# lc_filter_final.net
KiCad netlist of a schematic drawn in EAGLE
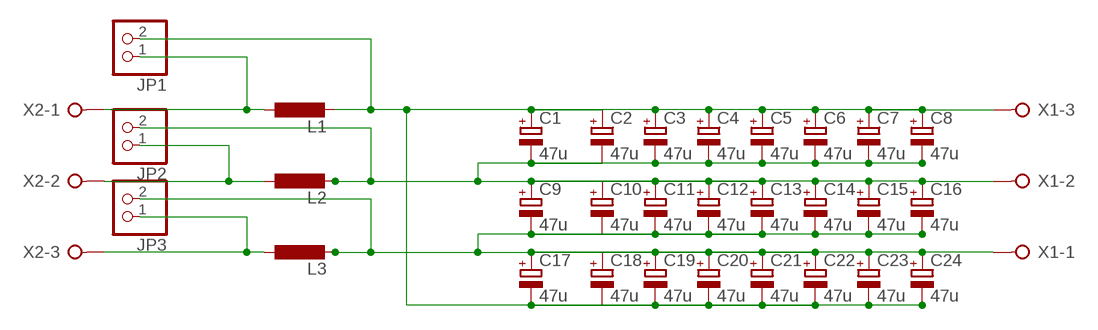
[diagram p0: schematic, sheet 1]

(export (version "E")
  (design (tool "Eeschema 10.0.6"))
  (components
    (comp (ref "C1")
      (value "47u")
      (footprint "eagle-import:E5-10,5")
      (libsource (lib "eagle-import") (part "CPOL-EUE5-10.5"))
    )
    (comp (ref "C2")
      (value "47u")
      (footprint "eagle-import:E5-10,5")
      (libsource (lib "eagle-import") (part "CPOL-EUE5-10.5"))
    )
    (comp (ref "C3")
      (value "47u")
      (footprint "eagle-import:E5-10,5")
      (libsource (lib "eagle-import") (part "CPOL-EUE5-10.5"))
    )
    (comp (ref "C4")
      (value "47u")
      (footprint "eagle-import:E5-10,5")
      (libsource (lib "eagle-import") (part "CPOL-EUE5-10.5"))
    )
    (comp (ref "C5")
      (value "47u")
      (footprint "eagle-import:E5-10,5")
      (libsource (lib "eagle-import") (part "CPOL-EUE5-10.5"))
    )
    (comp (ref "C6")
      (value "47u")
      (footprint "eagle-import:E5-10,5")
      (libsource (lib "eagle-import") (part "CPOL-EUE5-10.5"))
    )
    (comp (ref "C7")
      (value "47u")
      (footprint "eagle-import:E5-10,5")
      (libsource (lib "eagle-import") (part "CPOL-EUE5-10.5"))
    )
    (comp (ref "C8")
      (value "47u")
      (footprint "eagle-import:E5-10,5")
      (libsource (lib "eagle-import") (part "CPOL-EUE5-10.5"))
    )
    (comp (ref "C9")
      (value "47u")
      (footprint "eagle-import:E5-10,5")
      (libsource (lib "eagle-import") (part "CPOL-EUE5-10.5"))
    )
    (comp (ref "C10")
      (value "47u")
      (footprint "eagle-import:E5-10,5")
      (libsource (lib "eagle-import") (part "CPOL-EUE5-10.5"))
    )
    (comp (ref "C11")
      (value "47u")
      (footprint "eagle-import:E5-10,5")
      (libsource (lib "eagle-import") (part "CPOL-EUE5-10.5"))
    )
    (comp (ref "C12")
      (value "47u")
      (footprint "eagle-import:E5-10,5")
      (libsource (lib "eagle-import") (part "CPOL-EUE5-10.5"))
    )
    (comp (ref "C13")
      (value "47u")
      (footprint "eagle-import:E5-10,5")
      (libsource (lib "eagle-import") (part "CPOL-EUE5-10.5"))
    )
    (comp (ref "C14")
      (value "47u")
      (footprint "eagle-import:E5-10,5")
      (libsource (lib "eagle-import") (part "CPOL-EUE5-10.5"))
    )
    (comp (ref "C15")
      (value "47u")
      (footprint "eagle-import:E5-10,5")
      (libsource (lib "eagle-import") (part "CPOL-EUE5-10.5"))
    )
    (comp (ref "C16")
      (value "47u")
      (footprint "eagle-import:E5-10,5")
      (libsource (lib "eagle-import") (part "CPOL-EUE5-10.5"))
    )
    (comp (ref "C17")
      (value "47u")
      (footprint "eagle-import:E5-10,5")
      (libsource (lib "eagle-import") (part "CPOL-EUE5-10.5"))
    )
    (comp (ref "C18")
      (value "47u")
      (footprint "eagle-import:E5-10,5")
      (libsource (lib "eagle-import") (part "CPOL-EUE5-10.5"))
    )
    (comp (ref "C19")
      (value "47u")
      (footprint "eagle-import:E5-10,5")
      (libsource (lib "eagle-import") (part "CPOL-EUE5-10.5"))
    )
    (comp (ref "C20")
      (value "47u")
      (footprint "eagle-import:E5-10,5")
      (libsource (lib "eagle-import") (part "CPOL-EUE5-10.5"))
    )
    (comp (ref "C21")
      (value "47u")
      (footprint "eagle-import:E5-10,5")
      (libsource (lib "eagle-import") (part "CPOL-EUE5-10.5"))
    )
    (comp (ref "C22")
      (value "47u")
      (footprint "eagle-import:E5-10,5")
      (libsource (lib "eagle-import") (part "CPOL-EUE5-10.5"))
    )
    (comp (ref "C23")
      (value "47u")
      (footprint "eagle-import:E5-10,5")
      (libsource (lib "eagle-import") (part "CPOL-EUE5-10.5"))
    )
    (comp (ref "C24")
      (value "47u")
      (footprint "eagle-import:E5-10,5")
      (libsource (lib "eagle-import") (part "CPOL-EUE5-10.5"))
    )
    (comp (ref "JP1")
      (value "PINHD-1X2")
      (footprint "eagle-import:1X02")
      (libsource (lib "eagle-import") (part "PINHD-1X2"))
    )
    (comp (ref "JP2")
      (value "PINHD-1X2")
      (footprint "eagle-import:1X02")
      (libsource (lib "eagle-import") (part "PINHD-1X2"))
    )
    (comp (ref "JP3")
      (value "PINHD-1X2")
      (footprint "eagle-import:1X02")
      (libsource (lib "eagle-import") (part "PINHD-1X2"))
    )
    (comp (ref "L1")
      (value "L-EU6000-XXX-RC")
      (footprint "eagle-import:6000-XXXX-RC")
      (libsource (lib "eagle-import") (part "L-EU6000-XXX-RC"))
    )
    (comp (ref "L2")
      (value "L-EU6000-XXX-RC")
      (footprint "eagle-import:6000-XXXX-RC")
      (libsource (lib "eagle-import") (part "L-EU6000-XXX-RC"))
    )
    (comp (ref "L3")
      (value "L-EU6000-XXX-RC")
      (footprint "eagle-import:6000-XXXX-RC")
      (libsource (lib "eagle-import") (part "L-EU6000-XXX-RC"))
    )
    (comp (ref "X1")
      (value "W237-03P")
      (footprint "eagle-import:W237-133")
      (libsource (lib "eagle-import") (part "W237-03P"))
    )
    (comp (ref "X2")
      (value "W237-03P")
      (footprint "eagle-import:W237-133")
      (libsource (lib "eagle-import") (part "W237-03P"))
    )
  )
  (nets
    (net (code "1") (name "Net-(X1A-KL)") (class "Default")
      (node (ref "C10") (pin "-") (pinfunction "-_-") (pintype "passive"))
      (node (ref "C11") (pin "-") (pinfunction "-_-") (pintype "passive"))
      (node (ref "C12") (pin "-") (pinfunction "-_-") (pintype "passive"))
      (node (ref "C13") (pin "-") (pinfunction "-_-") (pintype "passive"))
      (node (ref "C14") (pin "-") (pinfunction "-_-") (pintype "passive"))
      (node (ref "C15") (pin "-") (pinfunction "-_-") (pintype "passive"))
      (node (ref "C16") (pin "-") (pinfunction "-_-") (pintype "passive"))
      (node (ref "C17") (pin "+") (pinfunction "+_+") (pintype "passive"))
      (node (ref "C18") (pin "+") (pinfunction "+_+") (pintype "passive"))
      (node (ref "C19") (pin "+") (pinfunction "+_+") (pintype "passive"))
      (node (ref "C20") (pin "+") (pinfunction "+_+") (pintype "passive"))
      (node (ref "C21") (pin "+") (pinfunction "+_+") (pintype "passive"))
      (node (ref "C22") (pin "+") (pinfunction "+_+") (pintype "passive"))
      (node (ref "C23") (pin "+") (pinfunction "+_+") (pintype "passive"))
      (node (ref "C24") (pin "+") (pinfunction "+_+") (pintype "passive"))
      (node (ref "C9") (pin "-") (pinfunction "-_-") (pintype "passive"))
      (node (ref "JP3") (pin "2") (pinfunction "2_2") (pintype "passive"))
      (node (ref "L3") (pin "2") (pinfunction "2_2") (pintype "passive"))
      (node (ref "X1") (pin "1") (pinfunction "KL_1") (pintype "passive"))
    )
    (net (code "2") (name "Net-(X1B-KL)") (class "Default")
      (node (ref "C1") (pin "-") (pinfunction "-_-") (pintype "passive"))
      (node (ref "C10") (pin "+") (pinfunction "+_+") (pintype "passive"))
      (node (ref "C11") (pin "+") (pinfunction "+_+") (pintype "passive"))
      (node (ref "C12") (pin "+") (pinfunction "+_+") (pintype "passive"))
      (node (ref "C13") (pin "+") (pinfunction "+_+") (pintype "passive"))
      (node (ref "C14") (pin "+") (pinfunction "+_+") (pintype "passive"))
      (node (ref "C15") (pin "+") (pinfunction "+_+") (pintype "passive"))
      (node (ref "C16") (pin "+") (pinfunction "+_+") (pintype "passive"))
      (node (ref "C2") (pin "-") (pinfunction "-_-") (pintype "passive"))
      (node (ref "C3") (pin "-") (pinfunction "-_-") (pintype "passive"))
      (node (ref "C4") (pin "-") (pinfunction "-_-") (pintype "passive"))
      (node (ref "C5") (pin "-") (pinfunction "-_-") (pintype "passive"))
      (node (ref "C6") (pin "-") (pinfunction "-_-") (pintype "passive"))
      (node (ref "C7") (pin "-") (pinfunction "-_-") (pintype "passive"))
      (node (ref "C8") (pin "-") (pinfunction "-_-") (pintype "passive"))
      (node (ref "C9") (pin "+") (pinfunction "+_+") (pintype "passive"))
      (node (ref "JP2") (pin "2") (pinfunction "2_2") (pintype "passive"))
      (node (ref "L2") (pin "2") (pinfunction "2_2") (pintype "passive"))
      (node (ref "X1") (pin "2") (pinfunction "KL_2") (pintype "passive"))
    )
    (net (code "3") (name "Net-(X1C-KL)") (class "Default")
      (node (ref "C1") (pin "+") (pinfunction "+_+") (pintype "passive"))
      (node (ref "C17") (pin "-") (pinfunction "-_-") (pintype "passive"))
      (node (ref "C18") (pin "-") (pinfunction "-_-") (pintype "passive"))
      (node (ref "C19") (pin "-") (pinfunction "-_-") (pintype "passive"))
      (node (ref "C2") (pin "+") (pinfunction "+_+") (pintype "passive"))
      (node (ref "C20") (pin "-") (pinfunction "-_-") (pintype "passive"))
      (node (ref "C21") (pin "-") (pinfunction "-_-") (pintype "passive"))
      (node (ref "C22") (pin "-") (pinfunction "-_-") (pintype "passive"))
      (node (ref "C23") (pin "-") (pinfunction "-_-") (pintype "passive"))
      (node (ref "C24") (pin "-") (pinfunction "-_-") (pintype "passive"))
      (node (ref "C3") (pin "+") (pinfunction "+_+") (pintype "passive"))
      (node (ref "C4") (pin "+") (pinfunction "+_+") (pintype "passive"))
      (node (ref "C5") (pin "+") (pinfunction "+_+") (pintype "passive"))
      (node (ref "C6") (pin "+") (pinfunction "+_+") (pintype "passive"))
      (node (ref "C7") (pin "+") (pinfunction "+_+") (pintype "passive"))
      (node (ref "C8") (pin "+") (pinfunction "+_+") (pintype "passive"))
      (node (ref "JP1") (pin "2") (pinfunction "2_2") (pintype "passive"))
      (node (ref "L1") (pin "2") (pinfunction "2_2") (pintype "passive"))
      (node (ref "X1") (pin "3") (pinfunction "KL_3") (pintype "passive"))
    )
    (net (code "4") (name "Net-(X2A-KL)") (class "Default")
      (node (ref "JP1") (pin "1") (pinfunction "1_1") (pintype "passive"))
      (node (ref "L1") (pin "1") (pinfunction "1_1") (pintype "passive"))
      (node (ref "X2") (pin "1") (pinfunction "KL_1") (pintype "passive"))
    )
    (net (code "5") (name "Net-(X2B-KL)") (class "Default")
      (node (ref "JP2") (pin "1") (pinfunction "1_1") (pintype "passive"))
      (node (ref "L2") (pin "1") (pinfunction "1_1") (pintype "passive"))
      (node (ref "X2") (pin "2") (pinfunction "KL_2") (pintype "passive"))
    )
    (net (code "6") (name "Net-(X2C-KL)") (class "Default")
      (node (ref "JP3") (pin "1") (pinfunction "1_1") (pintype "passive"))
      (node (ref "L3") (pin "1") (pinfunction "1_1") (pintype "passive"))
      (node (ref "X2") (pin "3") (pinfunction "KL_3") (pintype "passive"))
    )
  )
)
